# S04_SOM1_C_D.net
KiCad netlist of a schematic drawn in Altium Designer
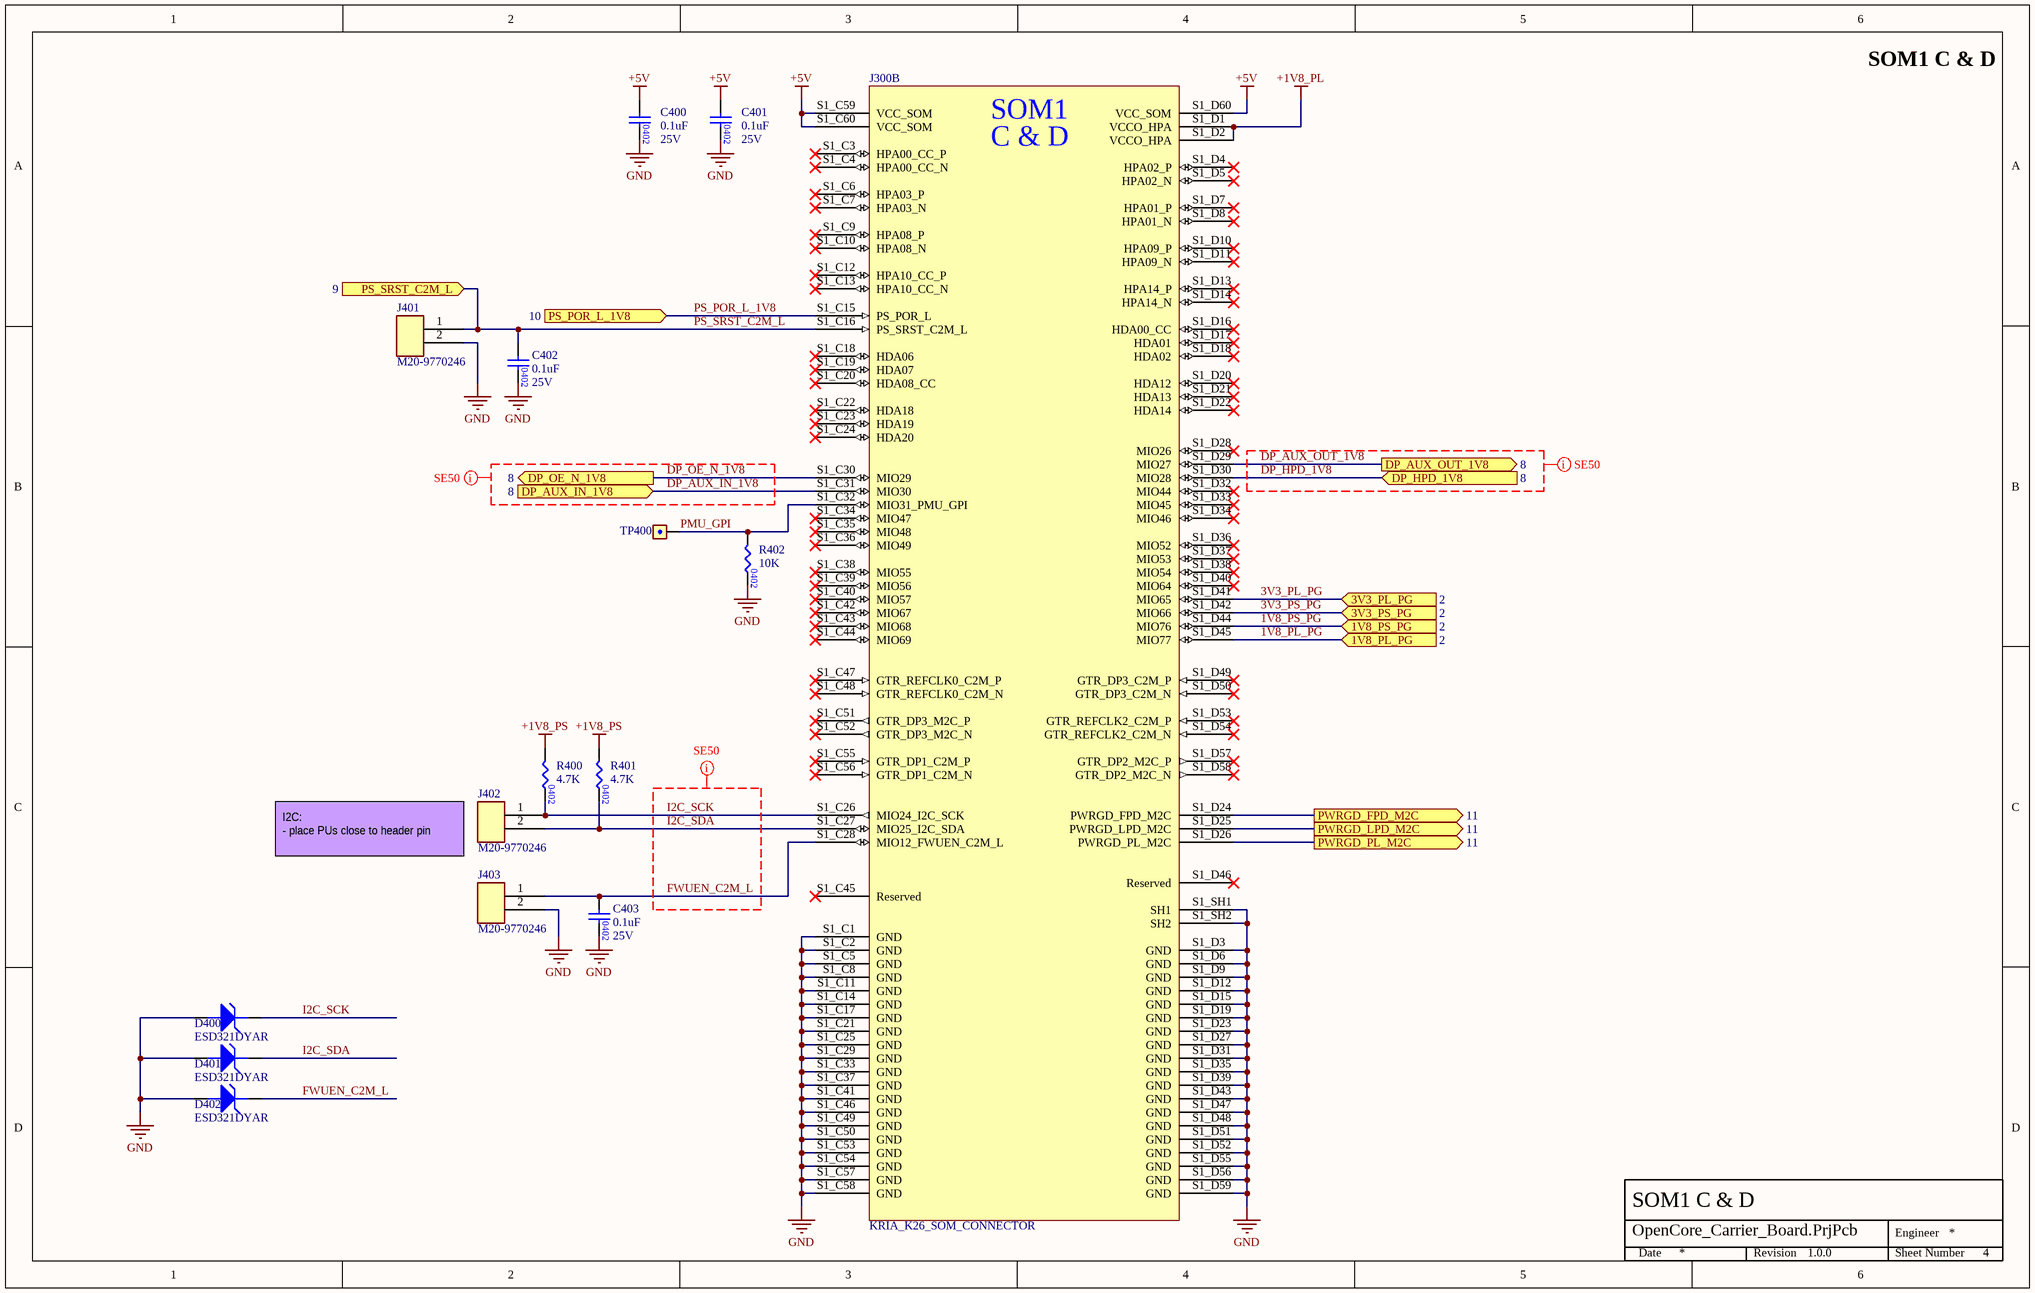
[diagram p0: S04_SOM1_C_D.SchDoc]

(export (version "E")
  (design (tool "Eeschema 10.0.6"))
  (components
    (comp (ref "C400")
      (value "0.1uF")
      (footprint "CAP0402")
      (description "CAP CER 0.1UF 25V X5R 0402")
      (fields
        (field (name "MANUFACTURER") "Samsung Electro-Mechanics")
        (field (name "TOLERANCE") "10%")
        (field (name "VOLTAGE RATING") "25V")
      )
      (libsource (lib "OpenCore_Sch_Lib") (part "CAP_CL05A104KA5NNNC"))
    )
    (comp (ref "C401")
      (value "0.1uF")
      (footprint "CAP0402")
      (description "CAP CER 0.1UF 25V X5R 0402")
      (fields
        (field (name "MANUFACTURER") "Samsung Electro-Mechanics")
        (field (name "TOLERANCE") "10%")
        (field (name "VOLTAGE RATING") "25V")
      )
      (libsource (lib "OpenCore_Sch_Lib") (part "CAP_CL05A104KA5NNNC"))
    )
    (comp (ref "C402")
      (value "0.1uF")
      (footprint "CAP0402")
      (description "CAP CER 0.1UF 25V X5R 0402")
      (fields
        (field (name "MANUFACTURER") "Samsung Electro-Mechanics")
        (field (name "TOLERANCE") "10%")
        (field (name "VOLTAGE RATING") "25V")
      )
      (libsource (lib "OpenCore_Sch_Lib") (part "CAP_CL05A104KA5NNNC"))
    )
    (comp (ref "C403")
      (value "0.1uF")
      (footprint "CAP0402")
      (description "CAP CER 0.1UF 25V X5R 0402")
      (fields
        (field (name "MANUFACTURER") "Samsung Electro-Mechanics")
        (field (name "TOLERANCE") "10%")
        (field (name "VOLTAGE RATING") "25V")
      )
      (libsource (lib "OpenCore_Sch_Lib") (part "CAP_CL05A104KA5NNNC"))
    )
    (comp (ref "D400")
      (value "ESD321DYAR")
      (footprint "TI_SOD523")
      (description "TVS DIODE 3.6VWM 6.3VC SOT5X3")
      (fields (field (name "MANFACTURER PART NUMBER") "ESD321DYAR"))
      (libsource (lib "OpenCore_Sch_Lib") (part "ESD321DYAR"))
    )
    (comp (ref "D401")
      (value "ESD321DYAR")
      (footprint "TI_SOD523")
      (description "TVS DIODE 3.6VWM 6.3VC SOT5X3")
      (fields (field (name "MANFACTURER PART NUMBER") "ESD321DYAR"))
      (libsource (lib "OpenCore_Sch_Lib") (part "ESD321DYAR"))
    )
    (comp (ref "D402")
      (value "ESD321DYAR")
      (footprint "TI_SOD523")
      (description "TVS DIODE 3.6VWM 6.3VC SOT5X3")
      (fields (field (name "MANFACTURER PART NUMBER") "ESD321DYAR"))
      (libsource (lib "OpenCore_Sch_Lib") (part "ESD321DYAR"))
    )
    (comp (ref "J300")
      (value "KRIA_K26_SOM_CONNECTOR")
      (footprint "KRIA_K26_SOM")
      (description "2 x 240 pos Samtec REF-226081-01")
      (fields
        (field (name "MANUFACTURER") "Samtec")
        (field (name "MANUFACTURER PART NUMBER") "REF-226081-01")
      )
      (libsource (lib "OpenCore_Sch_Lib") (part "KRIA_K26_SOM"))
    )
    (comp (ref "J401")
      (value "M20-9770246")
      (footprint "61300211121")
      (description "CONN HEADER VERT 2POS 2.54MM")
      (libsource (lib "OpenCore_Sch_Lib") (part "M20-9770246"))
    )
    (comp (ref "J402")
      (value "M20-9770246")
      (footprint "61300211121")
      (description "CONN HEADER VERT 2POS 2.54MM")
      (libsource (lib "OpenCore_Sch_Lib") (part "M20-9770246"))
    )
    (comp (ref "J403")
      (value "M20-9770246")
      (footprint "61300211121")
      (description "CONN HEADER VERT 2POS 2.54MM")
      (libsource (lib "OpenCore_Sch_Lib") (part "M20-9770246"))
    )
    (comp (ref "R400")
      (value "RES_0402")
      (footprint "RES0402")
      (description "RES 4.7K OHM 1% 1/16W 0402")
      (fields
        (field (name "MANUFACTURER") "YAGEO")
        (field (name "MANUFACTURER PART NUMBER") "RC0402FR-074K7L")
        (field (name "RESISTANCE") "4.7K")
      )
      (libsource (lib "OpenCore_Sch_Lib") (part ".RES_RC0402FR-074K7L"))
    )
    (comp (ref "R401")
      (value "RES_0402")
      (footprint "RES0402")
      (description "RES 4.7K OHM 1% 1/16W 0402")
      (fields
        (field (name "MANUFACTURER") "YAGEO")
        (field (name "MANUFACTURER PART NUMBER") "RC0402FR-074K7L")
        (field (name "RESISTANCE") "4.7K")
      )
      (libsource (lib "OpenCore_Sch_Lib") (part ".RES_RC0402FR-074K7L"))
    )
    (comp (ref "R402")
      (value "RES_0402")
      (footprint "RES0402")
      (description "RES 10K OHM 1% 1/16W 0402")
      (fields
        (field (name "MANUFACTURER") "YAGEO")
        (field (name "MANUFACTURER PART NUMBER") "RC0402FR-0710KL")
        (field (name "RESISTANCE") "10K")
      )
      (libsource (lib "OpenCore_Sch_Lib") (part ".RES_RC0402FR-0710KL"))
    )
    (comp (ref "TP400")
      (value "1mm Round Pad Testpoint")
      (footprint "TP_1MM")
      (libsource (lib "OpenCore_Sch_Lib") (part "TP_1MM"))
    )
  )
  (nets
    (net (code "1") (name "+1V8_PL") (class "Default")
      (node (ref "J300") (pin "S1_D1") (pinfunction "VCCO_HPA_S1_D1") (pintype "power_in"))
      (node (ref "J300") (pin "S1_D2") (pinfunction "VCCO_HPA_S1_D2") (pintype "power_in"))
    )
    (net (code "2") (name "+1V8_PS") (class "Default")
      (node (ref "R400") (pin "1") (pinfunction "1_1") (pintype "passive"))
      (node (ref "R401") (pin "1") (pinfunction "1_1") (pintype "passive"))
    )
    (net (code "3") (name "+5V") (class "Default")
      (node (ref "C400") (pin "1") (pinfunction "1_1") (pintype "passive"))
      (node (ref "C401") (pin "1") (pinfunction "1_1") (pintype "passive"))
      (node (ref "J300") (pin "S1_C59") (pinfunction "VCC_SOM_S1_C59") (pintype "power_in"))
      (node (ref "J300") (pin "S1_C60") (pinfunction "VCC_SOM_S1_C60") (pintype "power_in"))
      (node (ref "J300") (pin "S1_D60") (pinfunction "VCC_SOM_S1_D60") (pintype "power_in"))
    )
    (net (code "4") (name "/1V8_PL_PG") (class "Default")
      (node (ref "J300") (pin "S1_D45") (pinfunction "MIO77_S1_D45") (pintype "bidirectional"))
    )
    (net (code "5") (name "/1V8_PS_PG") (class "Default")
      (node (ref "J300") (pin "S1_D44") (pinfunction "MIO76_S1_D44") (pintype "bidirectional"))
    )
    (net (code "6") (name "/3V3_PL_PG") (class "Default")
      (node (ref "J300") (pin "S1_D41") (pinfunction "MIO65_S1_D41") (pintype "bidirectional"))
    )
    (net (code "7") (name "/3V3_PS_PG") (class "Default")
      (node (ref "J300") (pin "S1_D42") (pinfunction "MIO66_S1_D42") (pintype "bidirectional"))
    )
    (net (code "8") (name "/DP_AUX_IN_1V8") (class "Default")
      (node (ref "J300") (pin "S1_C31") (pinfunction "MIO30_S1_C31") (pintype "bidirectional"))
    )
    (net (code "9") (name "/DP_AUX_OUT_1V8") (class "Default")
      (node (ref "J300") (pin "S1_D29") (pinfunction "MIO27_S1_D29") (pintype "bidirectional"))
    )
    (net (code "10") (name "/DP_HPD_1V8") (class "Default")
      (node (ref "J300") (pin "S1_D30") (pinfunction "MIO28_S1_D30") (pintype "bidirectional"))
    )
    (net (code "11") (name "/DP_OE_N_1V8") (class "Default")
      (node (ref "J300") (pin "S1_C30") (pinfunction "MIO29_S1_C30") (pintype "bidirectional"))
    )
    (net (code "12") (name "/FWUEN_C2M_L") (class "Default")
      (node (ref "C403") (pin "1") (pinfunction "1_1") (pintype "passive"))
      (node (ref "D402") (pin "K") (pinfunction "Cathode_K") (pintype "passive"))
      (node (ref "J300") (pin "S1_C28") (pinfunction "MIO12_FWUEN_C2M_L_S1_C28") (pintype "bidirectional"))
      (node (ref "J403") (pin "1") (pinfunction "1_1") (pintype "passive"))
    )
    (net (code "13") (name "/I2C_SCK") (class "Default")
      (node (ref "D400") (pin "K") (pinfunction "Cathode_K") (pintype "passive"))
      (node (ref "J300") (pin "S1_C26") (pinfunction "MIO24_I2C_SCK_S1_C26") (pintype "output"))
      (node (ref "J402") (pin "1") (pinfunction "1_1") (pintype "passive"))
      (node (ref "R400") (pin "2") (pinfunction "2_2") (pintype "passive"))
    )
    (net (code "14") (name "/I2C_SDA") (class "Default")
      (node (ref "D401") (pin "K") (pinfunction "Cathode_K") (pintype "passive"))
      (node (ref "J300") (pin "S1_C27") (pinfunction "MIO25_I2C_SDA_S1_C27") (pintype "bidirectional"))
      (node (ref "J402") (pin "2") (pinfunction "2_2") (pintype "passive"))
      (node (ref "R401") (pin "2") (pinfunction "2_2") (pintype "passive"))
    )
    (net (code "15") (name "/PMU_GPI") (class "Default")
      (node (ref "J300") (pin "S1_C32") (pinfunction "MIO31_PMU_GPI_S1_C32") (pintype "bidirectional"))
      (node (ref "R402") (pin "1") (pinfunction "1_1") (pintype "passive"))
      (node (ref "TP400") (pin "1") (pinfunction "1_1") (pintype "passive"))
    )
    (net (code "16") (name "/PS_POR_L_1V8") (class "Default")
      (node (ref "J300") (pin "S1_C15") (pinfunction "PS_POR_L_S1_C15") (pintype "input"))
    )
    (net (code "17") (name "/PS_SRST_C2M_L") (class "Default")
      (node (ref "C402") (pin "1") (pinfunction "1_1") (pintype "passive"))
      (node (ref "J300") (pin "S1_C16") (pinfunction "PS_SRST_C2M_L_S1_C16") (pintype "input"))
      (node (ref "J401") (pin "1") (pinfunction "1_1") (pintype "passive"))
    )
    (net (code "18") (name "/PWRGD_FPD_M2C") (class "Default")
      (node (ref "J300") (pin "S1_D24") (pinfunction "PWRGD_FPD_M2C_S1_D24") (pintype "passive"))
    )
    (net (code "19") (name "/PWRGD_LPD_M2C") (class "Default")
      (node (ref "J300") (pin "S1_D25") (pinfunction "PWRGD_LPD_M2C_S1_D25") (pintype "passive"))
    )
    (net (code "20") (name "/PWRGD_PL_M2C") (class "Default")
      (node (ref "J300") (pin "S1_D26") (pinfunction "PWRGD_PL_M2C_S1_D26") (pintype "passive"))
    )
    (net (code "21") (name "GND") (class "Default")
      (node (ref "C400") (pin "2") (pinfunction "2_2") (pintype "passive"))
      (node (ref "C401") (pin "2") (pinfunction "2_2") (pintype "passive"))
      (node (ref "C402") (pin "2") (pinfunction "2_2") (pintype "passive"))
      (node (ref "C403") (pin "2") (pinfunction "2_2") (pintype "passive"))
      (node (ref "D400") (pin "A") (pinfunction "Anode_A") (pintype "passive"))
      (node (ref "D401") (pin "A") (pinfunction "Anode_A") (pintype "passive"))
      (node (ref "D402") (pin "A") (pinfunction "Anode_A") (pintype "passive"))
      (node (ref "J300") (pin "S1_C1") (pinfunction "GND_S1_C1") (pintype "power_in"))
      (node (ref "J300") (pin "S1_C11") (pinfunction "GND_S1_C11") (pintype "power_in"))
      (node (ref "J300") (pin "S1_C14") (pinfunction "GND_S1_C14") (pintype "power_in"))
      (node (ref "J300") (pin "S1_C17") (pinfunction "GND_S1_C17") (pintype "power_in"))
      (node (ref "J300") (pin "S1_C2") (pinfunction "GND_S1_C2") (pintype "power_in"))
      (node (ref "J300") (pin "S1_C21") (pinfunction "GND_S1_C21") (pintype "power_in"))
      (node (ref "J300") (pin "S1_C25") (pinfunction "GND_S1_C25") (pintype "power_in"))
      (node (ref "J300") (pin "S1_C29") (pinfunction "GND_S1_C29") (pintype "power_in"))
      (node (ref "J300") (pin "S1_C33") (pinfunction "GND_S1_C33") (pintype "power_in"))
      (node (ref "J300") (pin "S1_C37") (pinfunction "GND_S1_C37") (pintype "power_in"))
      (node (ref "J300") (pin "S1_C41") (pinfunction "GND_S1_C41") (pintype "power_in"))
      (node (ref "J300") (pin "S1_C46") (pinfunction "GND_S1_C46") (pintype "power_in"))
      (node (ref "J300") (pin "S1_C49") (pinfunction "GND_S1_C49") (pintype "power_in"))
      (node (ref "J300") (pin "S1_C5") (pinfunction "GND_S1_C5") (pintype "power_in"))
      (node (ref "J300") (pin "S1_C50") (pinfunction "GND_S1_C50") (pintype "power_in"))
      (node (ref "J300") (pin "S1_C53") (pinfunction "GND_S1_C53") (pintype "power_in"))
      (node (ref "J300") (pin "S1_C54") (pinfunction "GND_S1_C54") (pintype "power_in"))
      (node (ref "J300") (pin "S1_C57") (pinfunction "GND_S1_C57") (pintype "power_in"))
      (node (ref "J300") (pin "S1_C58") (pinfunction "GND_S1_C58") (pintype "power_in"))
      (node (ref "J300") (pin "S1_C8") (pinfunction "GND_S1_C8") (pintype "power_in"))
      (node (ref "J300") (pin "S1_D12") (pinfunction "GND_S1_D12") (pintype "power_in"))
      (node (ref "J300") (pin "S1_D15") (pinfunction "GND_S1_D15") (pintype "power_in"))
      (node (ref "J300") (pin "S1_D19") (pinfunction "GND_S1_D19") (pintype "power_in"))
      (node (ref "J300") (pin "S1_D23") (pinfunction "GND_S1_D23") (pintype "power_in"))
      (node (ref "J300") (pin "S1_D27") (pinfunction "GND_S1_D27") (pintype "power_in"))
      (node (ref "J300") (pin "S1_D3") (pinfunction "GND_S1_D3") (pintype "power_in"))
      (node (ref "J300") (pin "S1_D31") (pinfunction "GND_S1_D31") (pintype "power_in"))
      (node (ref "J300") (pin "S1_D35") (pinfunction "GND_S1_D35") (pintype "power_in"))
      (node (ref "J300") (pin "S1_D39") (pinfunction "GND_S1_D39") (pintype "power_in"))
      (node (ref "J300") (pin "S1_D43") (pinfunction "GND_S1_D43") (pintype "power_in"))
      (node (ref "J300") (pin "S1_D47") (pinfunction "GND_S1_D47") (pintype "power_in"))
      (node (ref "J300") (pin "S1_D48") (pinfunction "GND_S1_D48") (pintype "power_in"))
      (node (ref "J300") (pin "S1_D51") (pinfunction "GND_S1_D51") (pintype "power_in"))
      (node (ref "J300") (pin "S1_D52") (pinfunction "GND_S1_D52") (pintype "power_in"))
      (node (ref "J300") (pin "S1_D55") (pinfunction "GND_S1_D55") (pintype "power_in"))
      (node (ref "J300") (pin "S1_D56") (pinfunction "GND_S1_D56") (pintype "power_in"))
      (node (ref "J300") (pin "S1_D59") (pinfunction "GND_S1_D59") (pintype "power_in"))
      (node (ref "J300") (pin "S1_D6") (pinfunction "GND_S1_D6") (pintype "power_in"))
      (node (ref "J300") (pin "S1_D9") (pinfunction "GND_S1_D9") (pintype "power_in"))
      (node (ref "J300") (pin "S1_SH1") (pinfunction "SH1_S1_SH1") (pintype "passive"))
      (node (ref "J300") (pin "S1_SH2") (pinfunction "SH2_S1_SH2") (pintype "passive"))
      (node (ref "J401") (pin "2") (pinfunction "2_2") (pintype "passive"))
      (node (ref "J403") (pin "2") (pinfunction "2_2") (pintype "passive"))
      (node (ref "R402") (pin "2") (pinfunction "2_2") (pintype "passive"))
    )
    (net (code "22") (name "unconnected-(J300B-GTR_DP1_C2M_N-PadS1_C56)") (class "Default")
      (node (ref "J300") (pin "S1_C56") (pinfunction "GTR_DP1_C2M_N_S1_C56") (pintype "input+no_connect"))
    )
    (net (code "23") (name "unconnected-(J300B-GTR_DP1_C2M_P-PadS1_C55)") (class "Default")
      (node (ref "J300") (pin "S1_C55") (pinfunction "GTR_DP1_C2M_P_S1_C55") (pintype "input+no_connect"))
    )
    (net (code "24") (name "unconnected-(J300B-GTR_DP2_M2C_N-PadS1_D58)") (class "Default")
      (node (ref "J300") (pin "S1_D58") (pinfunction "GTR_DP2_M2C_N_S1_D58") (pintype "output+no_connect"))
    )
    (net (code "25") (name "unconnected-(J300B-GTR_DP2_M2C_P-PadS1_D57)") (class "Default")
      (node (ref "J300") (pin "S1_D57") (pinfunction "GTR_DP2_M2C_P_S1_D57") (pintype "output+no_connect"))
    )
    (net (code "26") (name "unconnected-(J300B-GTR_DP3_C2M_N-PadS1_D50)") (class "Default")
      (node (ref "J300") (pin "S1_D50") (pinfunction "GTR_DP3_C2M_N_S1_D50") (pintype "input+no_connect"))
    )
    (net (code "27") (name "unconnected-(J300B-GTR_DP3_C2M_P-PadS1_D49)") (class "Default")
      (node (ref "J300") (pin "S1_D49") (pinfunction "GTR_DP3_C2M_P_S1_D49") (pintype "input+no_connect"))
    )
    (net (code "28") (name "unconnected-(J300B-GTR_DP3_M2C_N-PadS1_C52)") (class "Default")
      (node (ref "J300") (pin "S1_C52") (pinfunction "GTR_DP3_M2C_N_S1_C52") (pintype "output+no_connect"))
    )
    (net (code "29") (name "unconnected-(J300B-GTR_DP3_M2C_P-PadS1_C51)") (class "Default")
      (node (ref "J300") (pin "S1_C51") (pinfunction "GTR_DP3_M2C_P_S1_C51") (pintype "output+no_connect"))
    )
    (net (code "30") (name "unconnected-(J300B-GTR_REFCLK0_C2M_N-PadS1_C48)") (class "Default")
      (node (ref "J300") (pin "S1_C48") (pinfunction "GTR_REFCLK0_C2M_N_S1_C48") (pintype "input+no_connect"))
    )
    (net (code "31") (name "unconnected-(J300B-GTR_REFCLK0_C2M_P-PadS1_C47)") (class "Default")
      (node (ref "J300") (pin "S1_C47") (pinfunction "GTR_REFCLK0_C2M_P_S1_C47") (pintype "input+no_connect"))
    )
    (net (code "32") (name "unconnected-(J300B-GTR_REFCLK2_C2M_N-PadS1_D54)") (class "Default")
      (node (ref "J300") (pin "S1_D54") (pinfunction "GTR_REFCLK2_C2M_N_S1_D54") (pintype "input+no_connect"))
    )
    (net (code "33") (name "unconnected-(J300B-GTR_REFCLK2_C2M_P-PadS1_D53)") (class "Default")
      (node (ref "J300") (pin "S1_D53") (pinfunction "GTR_REFCLK2_C2M_P_S1_D53") (pintype "input+no_connect"))
    )
    (net (code "34") (name "unconnected-(J300B-HDA00_CC-PadS1_D16)") (class "Default")
      (node (ref "J300") (pin "S1_D16") (pinfunction "HDA00_CC_S1_D16") (pintype "bidirectional+no_connect"))
    )
    (net (code "35") (name "unconnected-(J300B-HDA01-PadS1_D17)") (class "Default")
      (node (ref "J300") (pin "S1_D17") (pinfunction "HDA01_S1_D17") (pintype "bidirectional+no_connect"))
    )
    (net (code "36") (name "unconnected-(J300B-HDA02-PadS1_D18)") (class "Default")
      (node (ref "J300") (pin "S1_D18") (pinfunction "HDA02_S1_D18") (pintype "bidirectional+no_connect"))
    )
    (net (code "37") (name "unconnected-(J300B-HDA06-PadS1_C18)") (class "Default")
      (node (ref "J300") (pin "S1_C18") (pinfunction "HDA06_S1_C18") (pintype "bidirectional+no_connect"))
    )
    (net (code "38") (name "unconnected-(J300B-HDA07-PadS1_C19)") (class "Default")
      (node (ref "J300") (pin "S1_C19") (pinfunction "HDA07_S1_C19") (pintype "bidirectional+no_connect"))
    )
    (net (code "39") (name "unconnected-(J300B-HDA08_CC-PadS1_C20)") (class "Default")
      (node (ref "J300") (pin "S1_C20") (pinfunction "HDA08_CC_S1_C20") (pintype "bidirectional+no_connect"))
    )
    (net (code "40") (name "unconnected-(J300B-HDA12-PadS1_D20)") (class "Default")
      (node (ref "J300") (pin "S1_D20") (pinfunction "HDA12_S1_D20") (pintype "bidirectional+no_connect"))
    )
    (net (code "41") (name "unconnected-(J300B-HDA13-PadS1_D21)") (class "Default")
      (node (ref "J300") (pin "S1_D21") (pinfunction "HDA13_S1_D21") (pintype "bidirectional+no_connect"))
    )
    (net (code "42") (name "unconnected-(J300B-HDA14-PadS1_D22)") (class "Default")
      (node (ref "J300") (pin "S1_D22") (pinfunction "HDA14_S1_D22") (pintype "bidirectional+no_connect"))
    )
    (net (code "43") (name "unconnected-(J300B-HDA18-PadS1_C22)") (class "Default")
      (node (ref "J300") (pin "S1_C22") (pinfunction "HDA18_S1_C22") (pintype "bidirectional+no_connect"))
    )
    (net (code "44") (name "unconnected-(J300B-HDA19-PadS1_C23)") (class "Default")
      (node (ref "J300") (pin "S1_C23") (pinfunction "HDA19_S1_C23") (pintype "bidirectional+no_connect"))
    )
    (net (code "45") (name "unconnected-(J300B-HDA20-PadS1_C24)") (class "Default")
      (node (ref "J300") (pin "S1_C24") (pinfunction "HDA20_S1_C24") (pintype "bidirectional+no_connect"))
    )
    (net (code "46") (name "unconnected-(J300B-HPA00_CC_N-PadS1_C4)") (class "Default")
      (node (ref "J300") (pin "S1_C4") (pinfunction "HPA00_CC_N_S1_C4") (pintype "bidirectional+no_connect"))
    )
    (net (code "47") (name "unconnected-(J300B-HPA00_CC_P-PadS1_C3)") (class "Default")
      (node (ref "J300") (pin "S1_C3") (pinfunction "HPA00_CC_P_S1_C3") (pintype "bidirectional+no_connect"))
    )
    (net (code "48") (name "unconnected-(J300B-HPA01_N-PadS1_D8)") (class "Default")
      (node (ref "J300") (pin "S1_D8") (pinfunction "HPA01_N_S1_D8") (pintype "bidirectional+no_connect"))
    )
    (net (code "49") (name "unconnected-(J300B-HPA01_P-PadS1_D7)") (class "Default")
      (node (ref "J300") (pin "S1_D7") (pinfunction "HPA01_P_S1_D7") (pintype "bidirectional+no_connect"))
    )
    (net (code "50") (name "unconnected-(J300B-HPA02_N-PadS1_D5)") (class "Default")
      (node (ref "J300") (pin "S1_D5") (pinfunction "HPA02_N_S1_D5") (pintype "bidirectional+no_connect"))
    )
    (net (code "51") (name "unconnected-(J300B-HPA02_P-PadS1_D4)") (class "Default")
      (node (ref "J300") (pin "S1_D4") (pinfunction "HPA02_P_S1_D4") (pintype "bidirectional+no_connect"))
    )
    (net (code "52") (name "unconnected-(J300B-HPA03_N-PadS1_C7)") (class "Default")
      (node (ref "J300") (pin "S1_C7") (pinfunction "HPA03_N_S1_C7") (pintype "bidirectional+no_connect"))
    )
    (net (code "53") (name "unconnected-(J300B-HPA03_P-PadS1_C6)") (class "Default")
      (node (ref "J300") (pin "S1_C6") (pinfunction "HPA03_P_S1_C6") (pintype "bidirectional+no_connect"))
    )
    (net (code "54") (name "unconnected-(J300B-HPA08_N-PadS1_C10)") (class "Default")
      (node (ref "J300") (pin "S1_C10") (pinfunction "HPA08_N_S1_C10") (pintype "bidirectional+no_connect"))
    )
    (net (code "55") (name "unconnected-(J300B-HPA08_P-PadS1_C9)") (class "Default")
      (node (ref "J300") (pin "S1_C9") (pinfunction "HPA08_P_S1_C9") (pintype "bidirectional+no_connect"))
    )
    (net (code "56") (name "unconnected-(J300B-HPA09_N-PadS1_D11)") (class "Default")
      (node (ref "J300") (pin "S1_D11") (pinfunction "HPA09_N_S1_D11") (pintype "bidirectional+no_connect"))
    )
    (net (code "57") (name "unconnected-(J300B-HPA09_P-PadS1_D10)") (class "Default")
      (node (ref "J300") (pin "S1_D10") (pinfunction "HPA09_P_S1_D10") (pintype "bidirectional+no_connect"))
    )
    (net (code "58") (name "unconnected-(J300B-HPA10_CC_N-PadS1_C13)") (class "Default")
      (node (ref "J300") (pin "S1_C13") (pinfunction "HPA10_CC_N_S1_C13") (pintype "bidirectional+no_connect"))
    )
    (net (code "59") (name "unconnected-(J300B-HPA10_CC_P-PadS1_C12)") (class "Default")
      (node (ref "J300") (pin "S1_C12") (pinfunction "HPA10_CC_P_S1_C12") (pintype "bidirectional+no_connect"))
    )
    (net (code "60") (name "unconnected-(J300B-HPA14_N-PadS1_D14)") (class "Default")
      (node (ref "J300") (pin "S1_D14") (pinfunction "HPA14_N_S1_D14") (pintype "bidirectional+no_connect"))
    )
    (net (code "61") (name "unconnected-(J300B-HPA14_P-PadS1_D13)") (class "Default")
      (node (ref "J300") (pin "S1_D13") (pinfunction "HPA14_P_S1_D13") (pintype "bidirectional+no_connect"))
    )
    (net (code "62") (name "unconnected-(J300B-MIO26-PadS1_D28)") (class "Default")
      (node (ref "J300") (pin "S1_D28") (pinfunction "MIO26_S1_D28") (pintype "bidirectional+no_connect"))
    )
    (net (code "63") (name "unconnected-(J300B-MIO44-PadS1_D32)") (class "Default")
      (node (ref "J300") (pin "S1_D32") (pinfunction "MIO44_S1_D32") (pintype "bidirectional+no_connect"))
    )
    (net (code "64") (name "unconnected-(J300B-MIO45-PadS1_D33)") (class "Default")
      (node (ref "J300") (pin "S1_D33") (pinfunction "MIO45_S1_D33") (pintype "bidirectional+no_connect"))
    )
    (net (code "65") (name "unconnected-(J300B-MIO46-PadS1_D34)") (class "Default")
      (node (ref "J300") (pin "S1_D34") (pinfunction "MIO46_S1_D34") (pintype "bidirectional+no_connect"))
    )
    (net (code "66") (name "unconnected-(J300B-MIO47-PadS1_C34)") (class "Default")
      (node (ref "J300") (pin "S1_C34") (pinfunction "MIO47_S1_C34") (pintype "bidirectional+no_connect"))
    )
    (net (code "67") (name "unconnected-(J300B-MIO48-PadS1_C35)") (class "Default")
      (node (ref "J300") (pin "S1_C35") (pinfunction "MIO48_S1_C35") (pintype "bidirectional+no_connect"))
    )
    (net (code "68") (name "unconnected-(J300B-MIO49-PadS1_C36)") (class "Default")
      (node (ref "J300") (pin "S1_C36") (pinfunction "MIO49_S1_C36") (pintype "bidirectional+no_connect"))
    )
    (net (code "69") (name "unconnected-(J300B-MIO52-PadS1_D36)") (class "Default")
      (node (ref "J300") (pin "S1_D36") (pinfunction "MIO52_S1_D36") (pintype "bidirectional+no_connect"))
    )
    (net (code "70") (name "unconnected-(J300B-MIO53-PadS1_D37)") (class "Default")
      (node (ref "J300") (pin "S1_D37") (pinfunction "MIO53_S1_D37") (pintype "bidirectional+no_connect"))
    )
    (net (code "71") (name "unconnected-(J300B-MIO54-PadS1_D38)") (class "Default")
      (node (ref "J300") (pin "S1_D38") (pinfunction "MIO54_S1_D38") (pintype "bidirectional+no_connect"))
    )
    (net (code "72") (name "unconnected-(J300B-MIO55-PadS1_C38)") (class "Default")
      (node (ref "J300") (pin "S1_C38") (pinfunction "MIO55_S1_C38") (pintype "bidirectional+no_connect"))
    )
    (net (code "73") (name "unconnected-(J300B-MIO56-PadS1_C39)") (class "Default")
      (node (ref "J300") (pin "S1_C39") (pinfunction "MIO56_S1_C39") (pintype "bidirectional+no_connect"))
    )
    (net (code "74") (name "unconnected-(J300B-MIO57-PadS1_C40)") (class "Default")
      (node (ref "J300") (pin "S1_C40") (pinfunction "MIO57_S1_C40") (pintype "bidirectional+no_connect"))
    )
    (net (code "75") (name "unconnected-(J300B-MIO64-PadS1_D40)") (class "Default")
      (node (ref "J300") (pin "S1_D40") (pinfunction "MIO64_S1_D40") (pintype "bidirectional+no_connect"))
    )
    (net (code "76") (name "unconnected-(J300B-MIO67-PadS1_C42)") (class "Default")
      (node (ref "J300") (pin "S1_C42") (pinfunction "MIO67_S1_C42") (pintype "bidirectional+no_connect"))
    )
    (net (code "77") (name "unconnected-(J300B-MIO68-PadS1_C43)") (class "Default")
      (node (ref "J300") (pin "S1_C43") (pinfunction "MIO68_S1_C43") (pintype "bidirectional+no_connect"))
    )
    (net (code "78") (name "unconnected-(J300B-MIO69-PadS1_C44)") (class "Default")
      (node (ref "J300") (pin "S1_C44") (pinfunction "MIO69_S1_C44") (pintype "bidirectional+no_connect"))
    )
    (net (code "79") (name "unconnected-(J300B-Reserved-PadS1_C45)") (class "Default")
      (node (ref "J300") (pin "S1_C45") (pinfunction "Reserved_S1_C45") (pintype "passive+no_connect"))
    )
    (net (code "80") (name "unconnected-(J300B-Reserved-PadS1_D46)") (class "Default")
      (node (ref "J300") (pin "S1_D46") (pinfunction "Reserved_S1_D46") (pintype "passive+no_connect"))
    )
  )
)
